# v1_0.net
KiCad netlist of a schematic drawn in Altium Designer
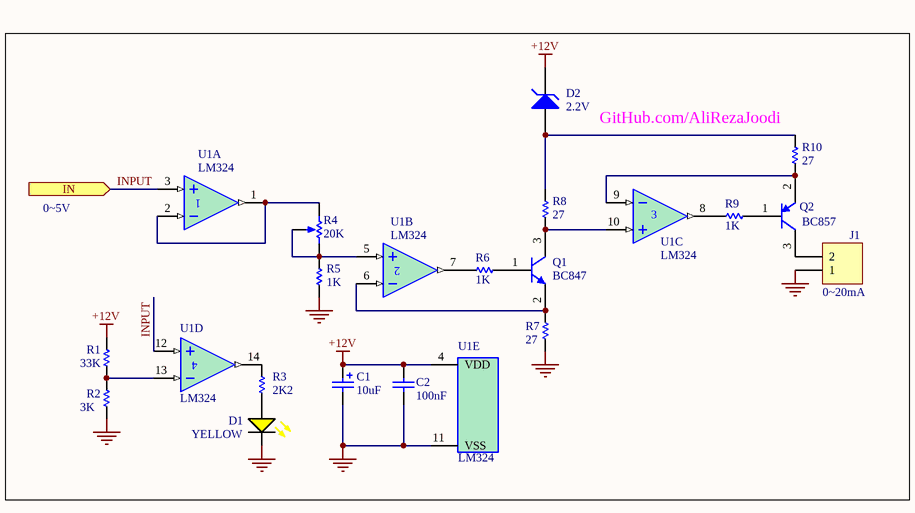
[diagram p0: v1.0.SchDoc]

(export (version "E")
  (design (tool "Eeschema 10.0.6"))
  (components
    (comp (ref "C1")
      (value "10uF")
      (footprint "Cap_B")
      (description "Polarized Capacitor (Radial)")
      (fields
        (field (name "MANUFACTURER") "Generic Components")
        (field (name "Comment") "Capacitor")
        (field (name "PUBLISHER") "Altium Limited")
      )
      (libsource (lib "Miscellaneous Devices") (part "Cap Pol1"))
    )
    (comp (ref "C2")
      (value "100nF")
      (footprint "0805")
      (description "Capacitor")
      (fields
        (field (name "MANUFACTURER") "Generic Components")
        (field (name "Comment") "Cap")
        (field (name "PUBLISHER") "Altium Limited")
      )
      (libsource (lib "Miscellaneous Devices") (part "Cap"))
    )
    (comp (ref "D1")
      (value "YELLOW")
      (footprint "LED_THD_3MM_YELLOW_R")
      (description "LED, Yellow")
      (fields (field (name "MANUFACTURER") "Generic Components") (field (name "PUBLISHER") "Altium Limited"))
      (libsource (lib "Display") (part "LED_YELLOW"))
    )
    (comp (ref "D2")
      (value "2.2V")
      (footprint "MELF-D3516-1406")
      (description "Zener Diode")
      (fields
        (field (name "MANUFACTURER") "Generic Components")
        (field (name "Comment") "LED")
        (field (name "PUBLISHER") "Altium Limited")
      )
      (libsource (lib "Miscellaneous Devices") (part "D Zener"))
    )
    (comp (ref "J1")
      (value "J17")
      (footprint "Fonics_2PIN_1")
      (description "Header, 2-Pin")
      (fields (field (name "PUBLISHER") "Altium Limited"))
      (libsource (lib "Miscellaneous Connectors") (part "Header 2"))
    )
    (comp (ref "Q1")
      (value "BC847")
      (footprint "SOT23-3N")
      (description "Silicon Bipolar Transistor")
      (fields (field (name "Comment") "NPN"))
      (libsource (lib "my Libraries") (part "BC847"))
    )
    (comp (ref "Q2")
      (value "BC857")
      (footprint "SOT23-3N")
      (description "Silicon Bipolar Transistor")
      (fields (field (name "Comment") "Q"))
      (libsource (lib "my Libraries") (part "BC857"))
    )
    (comp (ref "R1")
      (value "33K")
      (footprint "R_THD_AXIAL0.4(1/4W)")
      (description "Resistor")
      (libsource (lib "Passive") (part "Resistor"))
    )
    (comp (ref "R2")
      (value "3K")
      (footprint "R_THD_AXIAL0.4(1/4W)")
      (description "Resistor")
      (libsource (lib "Passive") (part "Resistor"))
    )
    (comp (ref "R3")
      (value "2K2")
      (footprint "R_THD_AXIAL0.4(1/4W)")
      (description "Resistor")
      (libsource (lib "Passive") (part "Resistor"))
    )
    (comp (ref "R4")
      (value "20K")
      (footprint "VR4_")
      (description "Potentiometer")
      (fields
        (field (name "MANUFACTURER") "Generic Components")
        (field (name "Comment") "RES")
        (field (name "PUBLISHER") "Altium Limited")
      )
      (libsource (lib "my Libraries") (part "RPot1"))
    )
    (comp (ref "R5")
      (value "1K")
      (footprint "R_THD_AXIAL0.4(1/4W)")
      (description "Resistor")
      (libsource (lib "Passive") (part "Resistor"))
    )
    (comp (ref "R6")
      (value "1K")
      (footprint "R_THD_AXIAL0.4(1/4W)")
      (description "Resistor")
      (libsource (lib "Passive") (part "Resistor"))
    )
    (comp (ref "R7")
      (value "27")
      (footprint "R_THD_AXIAL0.4(1/4W)")
      (description "Resistor")
      (libsource (lib "Passive") (part "Resistor"))
    )
    (comp (ref "R8")
      (value "27")
      (footprint "R_THD_AXIAL0.4(1/4W)")
      (description "Resistor")
      (libsource (lib "Passive") (part "Resistor"))
    )
    (comp (ref "R9")
      (value "1K")
      (footprint "R_THD_AXIAL0.4(1/4W)")
      (description "Resistor")
      (libsource (lib "Passive") (part "Resistor"))
    )
    (comp (ref "R10")
      (value "27")
      (footprint "R_THD_AXIAL0.4(1/4W)")
      (description "Resistor")
      (libsource (lib "Passive") (part "Resistor"))
    )
    (comp (ref "U1")
      (value "LM324")
      (footprint "DIP_14")
      (description "Quad Low-Power Operational Amplifier")
      (fields (field (name "PUBLISHER") "Altium Limited"))
      (libsource (lib "") (part "LM324_1"))
    )
  )
  (nets
    (net (code "1") (name "+12V") (class "Default")
      (node (ref "C1") (pin "1") (pinfunction "1_1") (pintype "passive"))
      (node (ref "C2") (pin "2") (pinfunction "2_2") (pintype "passive"))
      (node (ref "D2") (pin "2") (pinfunction "K_2") (pintype "passive"))
      (node (ref "R1") (pin "1") (pinfunction "1_1") (pintype "passive"))
      (node (ref "U1") (pin "4") (pinfunction "VDD_4") (pintype "passive"))
    )
    (net (code "2") (name "/INPUT") (class "Default")
      (node (ref "U1") (pin "12") (pinfunction "IN+_12") (pintype "input"))
      (node (ref "U1") (pin "3") (pinfunction "IN+_3") (pintype "input"))
    )
    (net (code "3") (name "GND") (class "Default")
      (node (ref "C1") (pin "2") (pinfunction "2_2") (pintype "passive"))
      (node (ref "C2") (pin "1") (pinfunction "1_1") (pintype "passive"))
      (node (ref "D1") (pin "2") (pinfunction "K_2") (pintype "passive"))
      (node (ref "J1") (pin "1") (pinfunction "1_1") (pintype "passive"))
      (node (ref "R2") (pin "2") (pinfunction "2_2") (pintype "passive"))
      (node (ref "R5") (pin "1") (pinfunction "1_1") (pintype "passive"))
      (node (ref "R7") (pin "1") (pinfunction "1_1") (pintype "passive"))
      (node (ref "U1") (pin "11") (pinfunction "VSS_11") (pintype "power_in"))
    )
    (net (code "4") (name "Net-(D1-A)") (class "Default")
      (node (ref "D1") (pin "1") (pinfunction "A_1") (pintype "passive"))
      (node (ref "R3") (pin "1") (pinfunction "1_1") (pintype "passive"))
    )
    (net (code "5") (name "Net-(D2-A)") (class "Default")
      (node (ref "D2") (pin "1") (pinfunction "A_1") (pintype "passive"))
      (node (ref "R10") (pin "2") (pinfunction "2_2") (pintype "passive"))
      (node (ref "R8") (pin "2") (pinfunction "2_2") (pintype "passive"))
    )
    (net (code "6") (name "Net-(Q1-B)") (class "Default")
      (node (ref "Q1") (pin "1") (pinfunction "B_1") (pintype "passive"))
      (node (ref "R6") (pin "2") (pinfunction "2_2") (pintype "passive"))
    )
    (net (code "7") (name "Net-(Q1-C)") (class "Default")
      (node (ref "Q1") (pin "3") (pinfunction "C_3") (pintype "passive"))
      (node (ref "R8") (pin "1") (pinfunction "1_1") (pintype "passive"))
      (node (ref "U1") (pin "10") (pinfunction "IN+_10") (pintype "input"))
    )
    (net (code "8") (name "Net-(Q1-E)") (class "Default")
      (node (ref "Q1") (pin "2") (pinfunction "E_2") (pintype "passive"))
      (node (ref "R7") (pin "2") (pinfunction "2_2") (pintype "passive"))
      (node (ref "U1") (pin "6") (pinfunction "IN-_6") (pintype "input"))
    )
    (net (code "9") (name "Net-(Q2-B)") (class "Default")
      (node (ref "Q2") (pin "1") (pinfunction "B_1") (pintype "passive"))
      (node (ref "R9") (pin "1") (pinfunction "1_1") (pintype "passive"))
    )
    (net (code "10") (name "Net-(Q2-C)") (class "Default")
      (node (ref "J1") (pin "2") (pinfunction "2_2") (pintype "passive"))
      (node (ref "Q2") (pin "3") (pinfunction "C_3") (pintype "passive"))
    )
    (net (code "11") (name "Net-(Q2-E)") (class "Default")
      (node (ref "Q2") (pin "2") (pinfunction "E_2") (pintype "passive"))
      (node (ref "R10") (pin "1") (pinfunction "1_1") (pintype "passive"))
      (node (ref "U1") (pin "9") (pinfunction "IN-_9") (pintype "input"))
    )
    (net (code "12") (name "Net-(R4-BOT)") (class "Default")
      (node (ref "R4") (pin "2") (pinfunction "BOT_2") (pintype "passive"))
      (node (ref "R4") (pin "3") (pinfunction "TAP_3") (pintype "passive"))
      (node (ref "R5") (pin "2") (pinfunction "2_2") (pintype "passive"))
      (node (ref "U1") (pin "5") (pinfunction "IN+_5") (pintype "input"))
    )
    (net (code "13") (name "Net-(R4-TOP)") (class "Default")
      (node (ref "R4") (pin "1") (pinfunction "TOP_1") (pintype "passive"))
      (node (ref "U1") (pin "1") (pinfunction "OUT_1") (pintype "output"))
      (node (ref "U1") (pin "2") (pinfunction "IN-_2") (pintype "input"))
    )
    (net (code "14") (name "Net-(U1B-OUT)") (class "Default")
      (node (ref "R6") (pin "1") (pinfunction "1_1") (pintype "passive"))
      (node (ref "U1") (pin "7") (pinfunction "OUT_7") (pintype "output"))
    )
    (net (code "15") (name "Net-(U1C-OUT)") (class "Default")
      (node (ref "R9") (pin "2") (pinfunction "2_2") (pintype "passive"))
      (node (ref "U1") (pin "8") (pinfunction "OUT_8") (pintype "output"))
    )
    (net (code "16") (name "Net-(U1D-IN-)") (class "Default")
      (node (ref "R1") (pin "2") (pinfunction "2_2") (pintype "passive"))
      (node (ref "R2") (pin "1") (pinfunction "1_1") (pintype "passive"))
      (node (ref "U1") (pin "13") (pinfunction "IN-_13") (pintype "input"))
    )
    (net (code "17") (name "Net-(U1D-OUT)") (class "Default")
      (node (ref "R3") (pin "2") (pinfunction "2_2") (pintype "passive"))
      (node (ref "U1") (pin "14") (pinfunction "OUT_14") (pintype "output"))
    )
  )
)
